# programmer-board-top.net
KiCad netlist of a schematic drawn in EAGLE
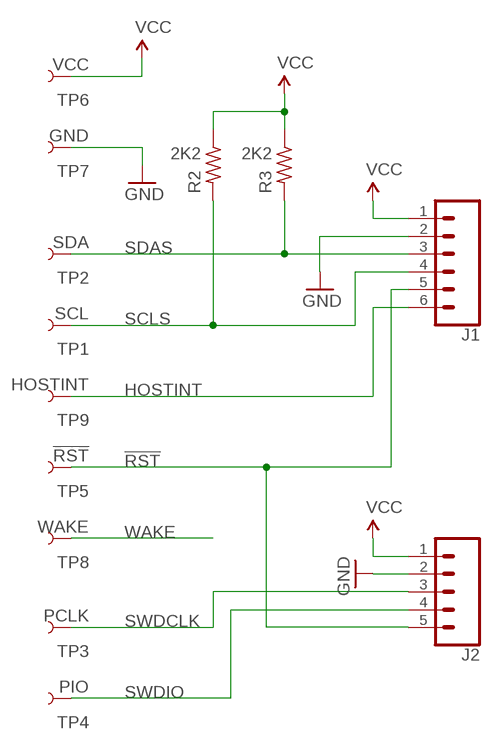
[diagram p0: schematic, sheet 1]

(export (version "E")
  (design (tool "Eeschema 10.0.6"))
  (components
    (comp (ref "J1")
      (value "CONN_06NO_SILK_FEMALE_PTH")
      (footprint "eagle-import:1X06_NO_SILK")
      (libsource (lib "eagle-import") (part "CONN_06NO_SILK_FEMALE_PTH"))
    )
    (comp (ref "J2")
      (value "CONN_05NO_SILK")
      (footprint "eagle-import:1X05_NO_SILK")
      (libsource (lib "eagle-import") (part "CONN_05NO_SILK"))
    )
    (comp (ref "R2")
      (value "2K2")
      (footprint "eagle-import:R0402_B")
      (libsource (lib "eagle-import") (part "R-US_"))
    )
    (comp (ref "R3")
      (value "2K2")
      (footprint "eagle-import:R0402_B")
      (libsource (lib "eagle-import") (part "R-US_"))
    )
    (comp (ref "TP1")
      (value "SCL")
      (footprint "eagle-import:PAD.03X.06")
      (libsource (lib "eagle-import") (part "TEST-POINT3X6"))
    )
    (comp (ref "TP2")
      (value "SDA")
      (footprint "eagle-import:PAD.03X.06")
      (libsource (lib "eagle-import") (part "TEST-POINT3X6"))
    )
    (comp (ref "TP3")
      (value "PCLK")
      (footprint "eagle-import:PAD.03X.06")
      (libsource (lib "eagle-import") (part "TEST-POINT3X6"))
    )
    (comp (ref "TP4")
      (value "PIO")
      (footprint "eagle-import:PAD.03X.06")
      (libsource (lib "eagle-import") (part "TEST-POINT3X6"))
    )
    (comp (ref "TP5")
      (value "!RST")
      (footprint "eagle-import:PAD.03X.06")
      (libsource (lib "eagle-import") (part "TEST-POINT3X6"))
    )
    (comp (ref "TP6")
      (value "VCC")
      (footprint "eagle-import:PAD.03X.06")
      (libsource (lib "eagle-import") (part "TEST-POINT3X6"))
    )
    (comp (ref "TP7")
      (value "GND")
      (footprint "eagle-import:PAD.03X.06")
      (libsource (lib "eagle-import") (part "TEST-POINT3X6"))
    )
    (comp (ref "TP8")
      (value "WAKE")
      (footprint "eagle-import:PAD.03X.06")
      (libsource (lib "eagle-import") (part "TEST-POINT3X6"))
    )
    (comp (ref "TP9")
      (value "HOSTINT")
      (footprint "eagle-import:PAD.03X.06")
      (libsource (lib "eagle-import") (part "TEST-POINT3X6"))
    )
  )
  (nets
    (net (code "1") (name "/HOSTINT") (class "Default")
      (node (ref "J1") (pin "6") (pinfunction "6_6") (pintype "passive"))
      (node (ref "TP9") (pin "1") (pinfunction "1_1") (pintype "bidirectional"))
    )
    (net (code "2") (name "/SCLS") (class "Default")
      (node (ref "J1") (pin "4") (pinfunction "4_4") (pintype "passive"))
      (node (ref "R2") (pin "2") (pinfunction "2_2") (pintype "passive"))
      (node (ref "TP1") (pin "1") (pinfunction "1_1") (pintype "bidirectional"))
    )
    (net (code "3") (name "/SDAS") (class "Default")
      (node (ref "J1") (pin "3") (pinfunction "3_3") (pintype "passive"))
      (node (ref "R3") (pin "2") (pinfunction "2_2") (pintype "passive"))
      (node (ref "TP2") (pin "1") (pinfunction "1_1") (pintype "bidirectional"))
    )
    (net (code "4") (name "/SWDCLK") (class "Default")
      (node (ref "J2") (pin "3") (pinfunction "3_3") (pintype "passive"))
      (node (ref "TP3") (pin "1") (pinfunction "1_1") (pintype "bidirectional"))
    )
    (net (code "5") (name "/SWDIO") (class "Default")
      (node (ref "J2") (pin "4") (pinfunction "4_4") (pintype "passive"))
      (node (ref "TP4") (pin "1") (pinfunction "1_1") (pintype "bidirectional"))
    )
    (net (code "6") (name "/WAKE") (class "Default")
      (node (ref "TP8") (pin "1") (pinfunction "1_1") (pintype "bidirectional"))
    )
    (net (code "7") (name "/~{RST}") (class "Default")
      (node (ref "J1") (pin "5") (pinfunction "5_5") (pintype "passive"))
      (node (ref "J2") (pin "5") (pinfunction "5_5") (pintype "passive"))
      (node (ref "TP5") (pin "1") (pinfunction "1_1") (pintype "bidirectional"))
    )
    (net (code "8") (name "GND") (class "Default")
      (node (ref "J1") (pin "2") (pinfunction "2_2") (pintype "passive"))
      (node (ref "J2") (pin "2") (pinfunction "2_2") (pintype "passive"))
      (node (ref "TP7") (pin "1") (pinfunction "1_1") (pintype "bidirectional"))
    )
    (net (code "9") (name "VCC") (class "Default")
      (node (ref "J1") (pin "1") (pinfunction "1_1") (pintype "passive"))
      (node (ref "J2") (pin "1") (pinfunction "1_1") (pintype "passive"))
      (node (ref "R2") (pin "1") (pinfunction "1_1") (pintype "passive"))
      (node (ref "R3") (pin "1") (pinfunction "1_1") (pintype "passive"))
      (node (ref "TP6") (pin "1") (pinfunction "1_1") (pintype "bidirectional"))
    )
  )
)
